# mcu.net
KiCad netlist of a schematic drawn in Altium Designer
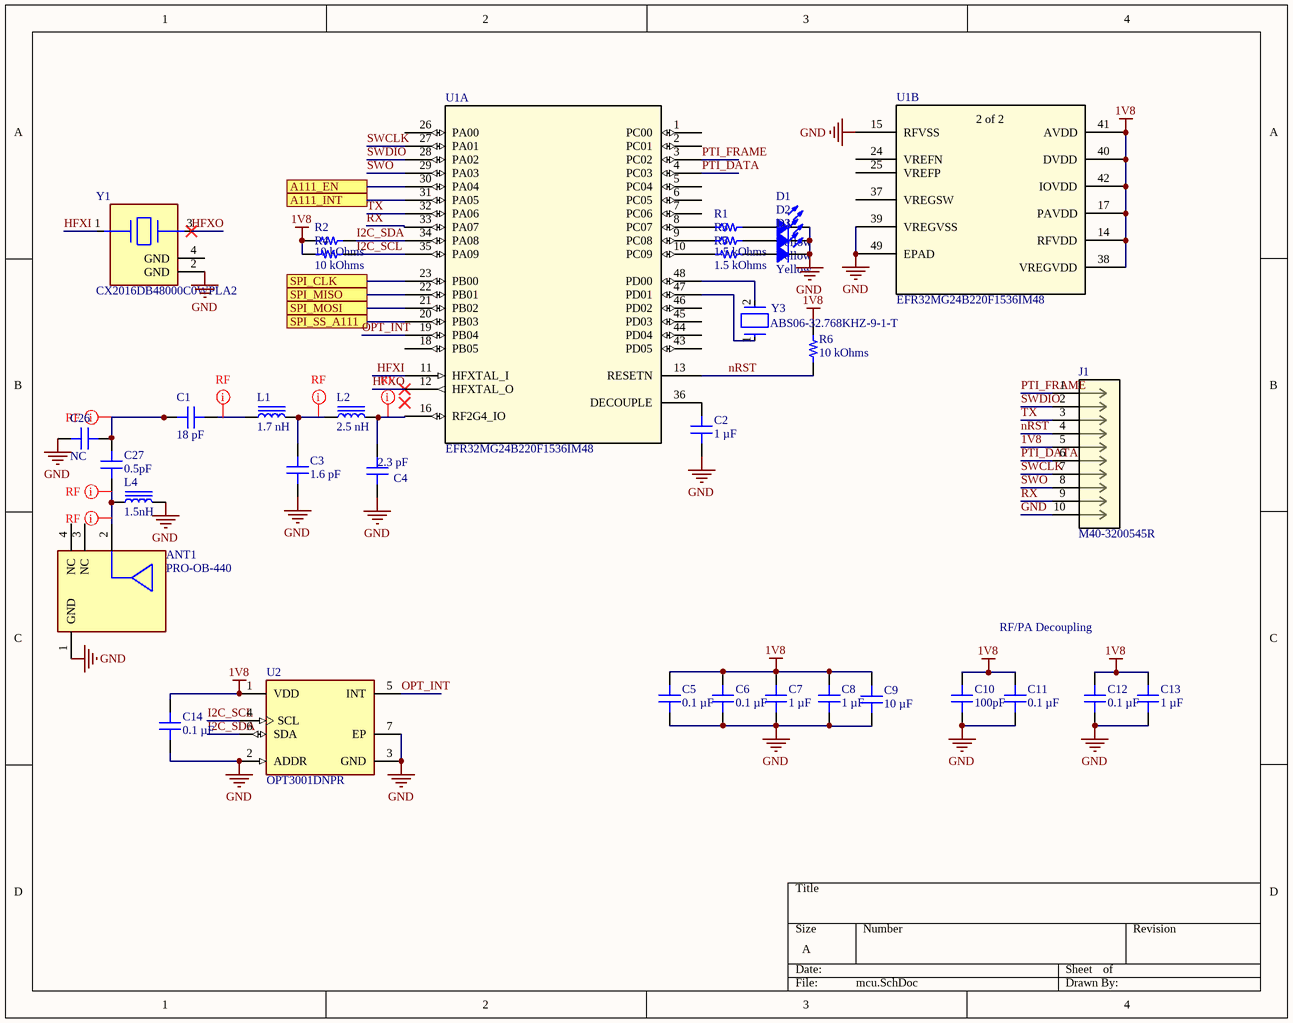
[diagram p0: mcu.SchDoc]

(export (version "E")
  (design (tool "Eeschema 10.0.6"))
  (components
    (comp (ref "ANT1")
      (value "PRO-OB-440")
      (footprint "FP-PRO-OB-440-MFG")
      (description "RF ANT 2.4GHZ STAMPED MET SLD")
      (fields
        (field (name "OCTOPART") "https://octopart.com/pro-ob-440-proant+ab-62921801")
        (field (name "MANUFACTURER") "ProAnt")
      )
      (libsource (lib "Altium Content Vault") (part "a5499d18dbada9eaf90098da4fe60e6"))
    )
    (comp (ref "C1")
      (value "18 pF")
      (footprint "CAP 0402_1005 RF")
      (description "CAP CER 18PF 200V NP0 0402")
      (fields
        (field (name "PART NUMBER") "600L180FW200T")
        (field (name "MANUFACTURER") "American Technical Ceramics")
      )
      (libsource (lib "Celestial Altium Library - altium_library") (part "Capacitor"))
    )
    (comp (ref "C2")
      (value "1 µF")
      (footprint "CAP 0402_1005")
      (description "CAP CER 0.1UF 4V X5R 0402")
      (fields (field (name "PART NUMBER") "C0402C104K7PAC7867") (field (name "MANUFACTURER") "KEMET"))
      (libsource (lib "Celestial Altium Library - altium_library") (part "Capacitor"))
    )
    (comp (ref "C3")
      (value "1.6 pF")
      (footprint "CAP 0402_1005 RF")
      (description "CAP CER 1.6PF 50V C0G/NP0 0402")
      (fields
        (field (name "PART NUMBER") "GJM1555C1H1R6CB01D")
        (field (name "MANUFACTURER") "Murata Electronics")
      )
      (libsource (lib "Celestial Altium Library - altium_library") (part "Capacitor"))
    )
    (comp (ref "C4")
      (value "2.3 pF")
      (footprint "CAP 0402_1005 RF")
      (description "CAP CER 2.3PF 50V C0G/NP0 0402")
      (fields
        (field (name "PART NUMBER") "GJM1555C1H2R3BB01D")
        (field (name "MANUFACTURER") "Murata Electronics")
      )
      (libsource (lib "Celestial Altium Library - altium_library") (part "Capacitor"))
    )
    (comp (ref "C5")
      (value "0.1 µF")
      (footprint "CAP 0402_1005")
      (description "CAP CER 0.1UF 4V X5R 0402")
      (fields (field (name "PART NUMBER") "C0402C104K7PAC7867") (field (name "MANUFACTURER") "KEMET"))
      (libsource (lib "Celestial Altium Library - altium_library") (part "Capacitor"))
    )
    (comp (ref "C6")
      (value "0.1 µF")
      (footprint "CAP 0402_1005")
      (description "CAP CER 0402 0.1UF 16V X7R 10%")
      (fields (field (name "PART NUMBER") "C0402C104K4RECAUTO") (field (name "MANUFACTURER") "KEMET"))
      (libsource (lib "Celestial Altium Library - altium_library") (part "Capacitor"))
    )
    (comp (ref "C7")
      (value "1 µF")
      (footprint "CAP 0402_1005")
      (description "CAP CER 1UF 10V X5R 0402")
      (fields (field (name "PART NUMBER") "LMK105BJ105MVHF") (field (name "MANUFACTURER") "Taiyo Yuden"))
      (libsource (lib "Celestial Altium Library - altium_library") (part "Capacitor"))
    )
    (comp (ref "C8")
      (value "1 µF")
      (footprint "CAP 0402_1005")
      (description "CAP CER 1UF 10V X5R 0402")
      (fields (field (name "PART NUMBER") "LMK105BJ105MVHF") (field (name "MANUFACTURER") "Taiyo Yuden"))
      (libsource (lib "Celestial Altium Library - altium_library") (part "Capacitor"))
    )
    (comp (ref "C9")
      (value "10 µF")
      (footprint "CAP 0603_1608")
      (description "CAP CER 10UF 6.3V X5R 0603")
      (fields
        (field (name "PART NUMBER") "GRM188R60J106ME47D")
        (field (name "MANUFACTURER") "Murata Electronics")
      )
      (libsource (lib "Celestial Altium Library - altium_library") (part "Capacitor"))
    )
    (comp (ref "C10")
      (value "100pF")
      (footprint "CAP 0402_1005")
      (description "CAP CER 100PF 6.3V X7R 0402")
      (fields (field (name "PART NUMBER") "04026C101KAT2A") (field (name "MANUFACTURER") "AVX Corporation"))
      (libsource (lib "Celestial Altium Library - altium_library") (part "Capacitor"))
    )
    (comp (ref "C11")
      (value "0.1 µF")
      (footprint "CAP 0402_1005")
      (description "CAP CER 0.1UF 4V X5R 0402")
      (fields (field (name "PART NUMBER") "C0402C104K7PAC7867") (field (name "MANUFACTURER") "KEMET"))
      (libsource (lib "Celestial Altium Library - altium_library") (part "Capacitor"))
    )
    (comp (ref "C12")
      (value "0.1 µF")
      (footprint "CAP 0402_1005")
      (description "CAP CER 0.1UF 4V X5R 0402")
      (fields (field (name "PART NUMBER") "C0402C104K7PAC7867") (field (name "MANUFACTURER") "KEMET"))
      (libsource (lib "Celestial Altium Library - altium_library") (part "Capacitor"))
    )
    (comp (ref "C13")
      (value "1 µF")
      (footprint "CAP 0402_1005")
      (description "CAP CER 1UF 4V X5R 0402")
      (fields
        (field (name "PART NUMBER") "CGB2T1X5R0G105M022BC")
        (field (name "MANUFACTURER") "TDK Corporation")
      )
      (libsource (lib "Celestial Altium Library - altium_library") (part "Capacitor"))
    )
    (comp (ref "C14")
      (value "0.1 µF")
      (footprint "CAP 0402_1005")
      (description "CAP CER 0.1UF 4V X5R 0402")
      (fields (field (name "PART NUMBER") "C0402C104K7PAC7867") (field (name "MANUFACTURER") "KEMET"))
      (libsource (lib "Celestial Altium Library - altium_library") (part "Capacitor"))
    )
    (comp (ref "C26")
      (value "NC")
      (footprint "CAP 0402_1005 RF")
      (description "CAP CER 18PF 200V NP0 0402")
      (fields
        (field (name "PART NUMBER") "600L180FW200T")
        (field (name "MANUFACTURER") "American Technical Ceramics")
      )
      (libsource (lib "Celestial Altium Library - altium_library") (part "Capacitor"))
    )
    (comp (ref "C27")
      (value "0.5pF")
      (footprint "CAP 0402_1005 RF")
      (description "CAP CER 18PF 200V NP0 0402")
      (fields
        (field (name "PART NUMBER") "600L180FW200T")
        (field (name "MANUFACTURER") "American Technical Ceramics")
      )
      (libsource (lib "Celestial Altium Library - altium_library") (part "Capacitor"))
    )
    (comp (ref "D1")
      (value "Yellow")
      (footprint "LED 0402_1005 YELLOW")
      (description "0402 YELLOW")
      (fields
        (field (name "PART NUMBER") "BL-HKC37A-AV-TRB")
        (field (name "MANUFACTURER") "American Bright Optoelectronics Corporation")
      )
      (libsource (lib "Celestial Altium Library - altium_library") (part "LED"))
    )
    (comp (ref "D2")
      (value "Yellow")
      (footprint "LED 0402_1005 YELLOW")
      (description "0402 YELLOW")
      (fields
        (field (name "PART NUMBER") "BL-HKC37A-AV-TRB")
        (field (name "MANUFACTURER") "American Bright Optoelectronics Corporation")
      )
      (libsource (lib "Celestial Altium Library - altium_library") (part "LED"))
    )
    (comp (ref "D3")
      (value "Yellow")
      (footprint "LED 0402_1005 YELLOW")
      (description "0402 YELLOW")
      (fields
        (field (name "PART NUMBER") "BL-HKC37A-AV-TRB")
        (field (name "MANUFACTURER") "American Bright Optoelectronics Corporation")
      )
      (libsource (lib "Celestial Altium Library - altium_library") (part "LED"))
    )
    (comp (ref "J1")
      (value "M40-3200545R")
      (footprint "CONN10_M40-3200545R_HRW")
      (description "No Description Available")
      (fields (field (name "COPYRIGHT") "Copyright (C) 2022 Ultra Librarian. All rights reserved."))
      (libsource (lib "M40-3200545R") (part "M40-3200545R"))
    )
    (comp (ref "L1")
      (value "1.7 nH")
      (footprint "IND 0402_1005 RF WW")
      (description "FIXED IND 1.7NH 1.15A 65MOHM SMD")
      (fields
        (field (name "PART NUMBER") "LQW15AN1N7D8ZD")
        (field (name "MANUFACTURER") "Murata Electronics")
      )
      (libsource (lib "Celestial Altium Library - altium_library") (part "Inductor"))
    )
    (comp (ref "L2")
      (value "2.5 nH")
      (footprint "IND 0402_1005 RF WW")
      (description "FIXED IND 2.5NH 850MA 50MOHM SMD")
      (fields
        (field (name "PART NUMBER") "LQW15AN2N5B00D")
        (field (name "MANUFACTURER") "Murata Electronics")
      )
      (libsource (lib "Celestial Altium Library - altium_library") (part "Inductor"))
    )
    (comp (ref "L4")
      (value "1.5nH")
      (footprint "IND 0402_1005 RF WW")
      (description "FIXED IND 1.7NH 1.15A 65MOHM SMD")
      (fields
        (field (name "PART NUMBER") "LQW15AN1N7D8ZD")
        (field (name "MANUFACTURER") "Murata Electronics")
      )
      (libsource (lib "Celestial Altium Library - altium_library") (part "Inductor"))
    )
    (comp (ref "R1")
      (value "~")
      (footprint "RES 0402_1005")
      (description "RES 1.5K OHM 0.05% 1/10W 0402")
      (fields
        (field (name "PART NUMBER") "ERA-2VRW1501X")
        (field (name "MANUFACTURER") "Panasonic Electronic Components")
      )
      (libsource (lib "Celestial Altium Library - altium_library") (part "Resistor"))
    )
    (comp (ref "R2")
      (value "10 kOhms")
      (footprint "RES 0402_1005")
      (description "RES 10K OHM 0.1% 1/10W 0402")
      (fields
        (field (name "PART NUMBER") "RP73PF1E10KBTD")
        (field (name "MANUFACTURER") "TE Connectivity Passive Product")
      )
      (libsource (lib "Celestial Altium Library - altium_library") (part "Resistor"))
    )
    (comp (ref "R3")
      (value "1.5 kOhms")
      (footprint "RES 0402_1005")
      (description "RES 1.5K OHM 0.05% 1/10W 0402")
      (fields
        (field (name "PART NUMBER") "ERA-2VRW1501X")
        (field (name "MANUFACTURER") "Panasonic Electronic Components")
      )
      (libsource (lib "Celestial Altium Library - altium_library") (part "Resistor"))
    )
    (comp (ref "R4")
      (value "10 kOhms")
      (footprint "RES 0402_1005")
      (description "RES 10K OHM 0.1% 1/10W 0402")
      (fields
        (field (name "PART NUMBER") "RP73PF1E10KBTD")
        (field (name "MANUFACTURER") "TE Connectivity Passive Product")
      )
      (libsource (lib "Celestial Altium Library - altium_library") (part "Resistor"))
    )
    (comp (ref "R5")
      (value "1.5 kOhms")
      (footprint "RES 0402_1005")
      (description "RES 1.5K OHM 0.05% 1/10W 0402")
      (fields
        (field (name "PART NUMBER") "ERA-2VRW1501X")
        (field (name "MANUFACTURER") "Panasonic Electronic Components")
      )
      (libsource (lib "Celestial Altium Library - altium_library") (part "Resistor"))
    )
    (comp (ref "R6")
      (value "10 kOhms")
      (footprint "RES 0402_1005")
      (description "RES 10K OHM 0.1% 1/10W 0402")
      (fields
        (field (name "PART NUMBER") "RP73PF1E10KBTD")
        (field (name "MANUFACTURER") "TE Connectivity Passive Product")
      )
      (libsource (lib "Celestial Altium Library - altium_library") (part "Resistor"))
    )
    (comp (ref "U1")
      (value "EFR32MG24B220F1536IM48")
      (footprint "QFN48_0p4_6sq_SIL")
      (description "No Description Available")
      (fields (field (name "COPYRIGHT") "Copyright (C) 2022 Ultra Librarian. All rights reserved."))
      (libsource (lib "EFR32MG24B220F1536IM48") (part "EFR32MG24B220F1536IM48"))
    )
    (comp (ref "U2")
      (value "OPT3001DNPR")
      (footprint "FP-DNP0006A-MFG")
      (description "SENSOR OPT 550NM AMBIENT 6USON")
      (fields
        (field (name "OCTOPART") "https://octopart.com/opt3001dnpr-texas+instruments-47324050")
        (field (name "MANUFACTURER") "Texas Instruments")
      )
      (libsource (lib "Altium Content Vault") (part "6d36863dc75c3adee7e1b5a0d97a822"))
    )
    (comp (ref "Y1")
      (value "CX2016DB48000C0WPLA2")
      (footprint "FP-CX2016DB48000C0WPLA2-MFG")
      (description "CRYSTAL 48.0000MHZ 7PF SMD")
      (fields
        (field (name "TOLERANCE") "20ppm")
        (field (name "OCTOPART") "https://octopart.com/cx2016db48000c0wpla2-avx+%2F+kyocera-52876167")
      )
      (libsource (lib "Altium Content Vault") (part "5d94e547cd785c846f3f8944f2e9776"))
    )
    (comp (ref "Y3")
      (value "ABS06-32.768KHZ-9-1-T")
      (footprint "FP-ABS06-MFG")
      (description "Crystal 32.768kHz ±10ppm (Tol) 9pF FUND 90kΩ 2-Pin Mini-CSMD T/R")
      (fields (field (name "TOLERANCE") "10ppm"))
      (libsource (lib "Altium Content Vault") (part "c23a69dc6c9e2f18f2079038eb95dd1"))
    )
  )
  (nets
    (net (code "1") (name "/A111_EN") (class "Default")
      (node (ref "U1") (pin "30") (pinfunction "PA04_30") (pintype "bidirectional"))
    )
    (net (code "2") (name "/A111_INT") (class "Default")
      (node (ref "U1") (pin "31") (pinfunction "PA05_31") (pintype "bidirectional"))
    )
    (net (code "3") (name "/HFXI") (class "Default")
      (node (ref "U1") (pin "11") (pinfunction "HFXTAL_I_11") (pintype "input"))
      (node (ref "Y1") (pin "1") (pinfunction "1_HOT_1") (pintype "passive"))
    )
    (net (code "4") (name "/HFXO") (class "Default")
      (node (ref "U1") (pin "12") (pinfunction "HFXTAL_O_12") (pintype "output"))
      (node (ref "Y1") (pin "3") (pinfunction "2_HOT_3") (pintype "passive"))
    )
    (net (code "5") (name "/I2C_SCL") (class "Default")
      (node (ref "R4") (pin "1") (pinfunction "1_1") (pintype "passive"))
      (node (ref "U1") (pin "35") (pinfunction "PA09_35") (pintype "bidirectional"))
      (node (ref "U2") (pin "4") (pinfunction "SCL_4") (pintype "input"))
    )
    (net (code "6") (name "/I2C_SDA") (class "Default")
      (node (ref "R2") (pin "1") (pinfunction "1_1") (pintype "passive"))
      (node (ref "U1") (pin "34") (pinfunction "PA08_34") (pintype "bidirectional"))
      (node (ref "U2") (pin "6") (pinfunction "SDA_6") (pintype "bidirectional"))
    )
    (net (code "7") (name "/OPT_INT") (class "Default")
      (node (ref "U1") (pin "19") (pinfunction "PB04_19") (pintype "bidirectional"))
      (node (ref "U2") (pin "5") (pinfunction "INT_5") (pintype "open_collector"))
    )
    (net (code "8") (name "/PTI_DATA") (class "Default")
      (node (ref "J1") (pin "6") (pinfunction "6_6") (pintype "passive"))
      (node (ref "U1") (pin "4") (pinfunction "PC03_4") (pintype "bidirectional"))
    )
    (net (code "9") (name "/PTI_FRAME") (class "Default")
      (node (ref "J1") (pin "1") (pinfunction "1_1") (pintype "passive"))
      (node (ref "U1") (pin "3") (pinfunction "PC02_3") (pintype "bidirectional"))
    )
    (net (code "10") (name "/RX") (class "Default")
      (node (ref "J1") (pin "9") (pinfunction "9_9") (pintype "passive"))
      (node (ref "U1") (pin "33") (pinfunction "PA07_33") (pintype "bidirectional"))
    )
    (net (code "11") (name "/SPI_CLK") (class "Default")
      (node (ref "U1") (pin "23") (pinfunction "PB00_23") (pintype "bidirectional"))
    )
    (net (code "12") (name "/SPI_MISO") (class "Default")
      (node (ref "U1") (pin "22") (pinfunction "PB01_22") (pintype "bidirectional"))
    )
    (net (code "13") (name "/SPI_MOSI") (class "Default")
      (node (ref "U1") (pin "21") (pinfunction "PB02_21") (pintype "bidirectional"))
    )
    (net (code "14") (name "/SPI_SS_A111") (class "Default")
      (node (ref "U1") (pin "20") (pinfunction "PB03_20") (pintype "bidirectional"))
    )
    (net (code "15") (name "/SWCLK") (class "Default")
      (node (ref "J1") (pin "7") (pinfunction "7_7") (pintype "passive"))
      (node (ref "U1") (pin "27") (pinfunction "PA01_27") (pintype "bidirectional"))
    )
    (net (code "16") (name "/SWDIO") (class "Default")
      (node (ref "J1") (pin "2") (pinfunction "2_2") (pintype "passive"))
      (node (ref "U1") (pin "28") (pinfunction "PA02_28") (pintype "bidirectional"))
    )
    (net (code "17") (name "/SWO") (class "Default")
      (node (ref "J1") (pin "8") (pinfunction "8_8") (pintype "passive"))
      (node (ref "U1") (pin "29") (pinfunction "PA03_29") (pintype "bidirectional"))
    )
    (net (code "18") (name "/TX") (class "Default")
      (node (ref "J1") (pin "3") (pinfunction "3_3") (pintype "passive"))
      (node (ref "U1") (pin "32") (pinfunction "PA06_32") (pintype "bidirectional"))
    )
    (net (code "19") (name "/nRST") (class "Default")
      (node (ref "J1") (pin "4") (pinfunction "4_4") (pintype "passive"))
      (node (ref "R6") (pin "2") (pinfunction "2_2") (pintype "passive"))
      (node (ref "U1") (pin "13") (pinfunction "RESETN_13") (pintype "passive"))
    )
    (net (code "20") (name "1V8") (class "Default")
      (node (ref "C10") (pin "2") (pinfunction "2_2") (pintype "passive"))
      (node (ref "C11") (pin "2") (pinfunction "2_2") (pintype "passive"))
      (node (ref "C12") (pin "2") (pinfunction "2_2") (pintype "passive"))
      (node (ref "C13") (pin "2") (pinfunction "2_2") (pintype "passive"))
      (node (ref "C14") (pin "2") (pinfunction "2_2") (pintype "passive"))
      (node (ref "C5") (pin "2") (pinfunction "2_2") (pintype "passive"))
      (node (ref "C6") (pin "2") (pinfunction "2_2") (pintype "passive"))
      (node (ref "C7") (pin "2") (pinfunction "2_2") (pintype "passive"))
      (node (ref "C8") (pin "2") (pinfunction "2_2") (pintype "passive"))
      (node (ref "C9") (pin "2") (pinfunction "2_2") (pintype "passive"))
      (node (ref "J1") (pin "5") (pinfunction "5_5") (pintype "passive"))
      (node (ref "R2") (pin "2") (pinfunction "2_2") (pintype "passive"))
      (node (ref "R4") (pin "2") (pinfunction "2_2") (pintype "passive"))
      (node (ref "R6") (pin "1") (pinfunction "1_1") (pintype "passive"))
      (node (ref "U1") (pin "14") (pinfunction "RFVDD_14") (pintype "power_in"))
      (node (ref "U1") (pin "17") (pinfunction "PAVDD_17") (pintype "power_in"))
      (node (ref "U1") (pin "38") (pinfunction "VREGVDD_38") (pintype "power_in"))
      (node (ref "U1") (pin "40") (pinfunction "DVDD_40") (pintype "power_in"))
      (node (ref "U1") (pin "41") (pinfunction "AVDD_41") (pintype "power_in"))
      (node (ref "U1") (pin "42") (pinfunction "IOVDD_42") (pintype "power_in"))
      (node (ref "U2") (pin "1") (pinfunction "VDD_1") (pintype "power_in"))
    )
    (net (code "21") (name "GND") (class "Default")
      (node (ref "ANT1") (pin "1") (pinfunction "GND_1") (pintype "power_in"))
      (node (ref "C10") (pin "1") (pinfunction "1_1") (pintype "passive"))
      (node (ref "C11") (pin "1") (pinfunction "1_1") (pintype "passive"))
      (node (ref "C12") (pin "1") (pinfunction "1_1") (pintype "passive"))
      (node (ref "C13") (pin "1") (pinfunction "1_1") (pintype "passive"))
      (node (ref "C14") (pin "1") (pinfunction "1_1") (pintype "passive"))
      (node (ref "C2") (pin "1") (pinfunction "1_1") (pintype "passive"))
      (node (ref "C26") (pin "1") (pinfunction "1_1") (pintype "passive"))
      (node (ref "C3") (pin "1") (pinfunction "1_1") (pintype "passive"))
      (node (ref "C4") (pin "1") (pinfunction "1_1") (pintype "passive"))
      (node (ref "C5") (pin "1") (pinfunction "1_1") (pintype "passive"))
      (node (ref "C6") (pin "1") (pinfunction "1_1") (pintype "passive"))
      (node (ref "C7") (pin "1") (pinfunction "1_1") (pintype "passive"))
      (node (ref "C8") (pin "1") (pinfunction "1_1") (pintype "passive"))
      (node (ref "C9") (pin "1") (pinfunction "1_1") (pintype "passive"))
      (node (ref "D1") (pin "2") (pinfunction "2_2") (pintype "passive"))
      (node (ref "D2") (pin "2") (pinfunction "2_2") (pintype "passive"))
      (node (ref "D3") (pin "2") (pinfunction "2_2") (pintype "passive"))
      (node (ref "J1") (pin "10") (pinfunction "10_10") (pintype "passive"))
      (node (ref "L4") (pin "2") (pinfunction "2_2") (pintype "passive"))
      (node (ref "U1") (pin "15") (pinfunction "RFVSS_15") (pintype "power_in"))
      (node (ref "U1") (pin "39") (pinfunction "VREGVSS_39") (pintype "power_in"))
      (node (ref "U1") (pin "49") (pinfunction "EPAD_49") (pintype "passive"))
      (node (ref "U2") (pin "2") (pinfunction "ADDR_2") (pintype "input"))
      (node (ref "U2") (pin "3") (pinfunction "GND_3") (pintype "power_in"))
      (node (ref "U2") (pin "7") (pinfunction "EP_7") (pintype "power_in"))
      (node (ref "Y1") (pin "2") (pinfunction "GND_2") (pintype "power_in"))
    )
    (net (code "22") (name "Net-(ANT1-RF_FEED)") (class "Default")
      (node (ref "ANT1") (pin "2") (pinfunction "RF_FEED_2") (pintype "passive"))
      (node (ref "C27") (pin "1") (pinfunction "1_1") (pintype "passive"))
      (node (ref "L4") (pin "1") (pinfunction "1_1") (pintype "passive"))
    )
    (net (code "23") (name "Net-(C1-Pad1)") (class "Default")
      (node (ref "C1") (pin "1") (pinfunction "1_1") (pintype "passive"))
      (node (ref "C26") (pin "2") (pinfunction "2_2") (pintype "passive"))
      (node (ref "C27") (pin "2") (pinfunction "2_2") (pintype "passive"))
    )
    (net (code "24") (name "Net-(C1-Pad2)") (class "Default")
      (node (ref "C1") (pin "2") (pinfunction "2_2") (pintype "passive"))
      (node (ref "L1") (pin "1") (pinfunction "1_1") (pintype "passive"))
    )
    (net (code "25") (name "Net-(C3-Pad2)") (class "Default")
      (node (ref "C3") (pin "2") (pinfunction "2_2") (pintype "passive"))
      (node (ref "L1") (pin "2") (pinfunction "2_2") (pintype "passive"))
      (node (ref "L2") (pin "1") (pinfunction "1_1") (pintype "passive"))
    )
    (net (code "26") (name "Net-(D1-Pad1)") (class "Default")
      (node (ref "D1") (pin "1") (pinfunction "1_1") (pintype "passive"))
      (node (ref "R1") (pin "1") (pinfunction "1_1") (pintype "passive"))
    )
    (net (code "27") (name "Net-(D2-Pad1)") (class "Default")
      (node (ref "D2") (pin "1") (pinfunction "1_1") (pintype "passive"))
      (node (ref "R3") (pin "1") (pinfunction "1_1") (pintype "passive"))
    )
    (net (code "28") (name "Net-(D3-Pad1)") (class "Default")
      (node (ref "D3") (pin "1") (pinfunction "1_1") (pintype "passive"))
      (node (ref "R5") (pin "1") (pinfunction "1_1") (pintype "passive"))
    )
    (net (code "29") (name "Net-(U1A-DECOUPLE)") (class "Default")
      (node (ref "C2") (pin "2") (pinfunction "2_2") (pintype "passive"))
      (node (ref "U1") (pin "36") (pinfunction "DECOUPLE_36") (pintype "passive"))
    )
    (net (code "30") (name "Net-(U1A-PC07)") (class "Default")
      (node (ref "R1") (pin "2") (pinfunction "2_2") (pintype "passive"))
      (node (ref "U1") (pin "8") (pinfunction "PC07_8") (pintype "bidirectional"))
    )
    (net (code "31") (name "Net-(U1A-PC08)") (class "Default")
      (node (ref "R3") (pin "2") (pinfunction "2_2") (pintype "passive"))
      (node (ref "U1") (pin "9") (pinfunction "PC08_9") (pintype "bidirectional"))
    )
    (net (code "32") (name "Net-(U1A-PC09)") (class "Default")
      (node (ref "R5") (pin "2") (pinfunction "2_2") (pintype "passive"))
      (node (ref "U1") (pin "10") (pinfunction "PC09_10") (pintype "bidirectional"))
    )
    (net (code "33") (name "Net-(U1A-PD00)") (class "Default")
      (node (ref "U1") (pin "48") (pinfunction "PD00_48") (pintype "bidirectional"))
      (node (ref "Y3") (pin "2") (pinfunction "2_2") (pintype "passive"))
    )
    (net (code "34") (name "Net-(U1A-PD01)") (class "Default")
      (node (ref "U1") (pin "47") (pinfunction "PD01_47") (pintype "bidirectional"))
      (node (ref "Y3") (pin "1") (pinfunction "1_1") (pintype "passive"))
    )
    (net (code "35") (name "Net-(U1A-RF2G4_IO)") (class "Default")
      (node (ref "C4") (pin "2") (pinfunction "2_2") (pintype "passive"))
      (node (ref "L2") (pin "2") (pinfunction "2_2") (pintype "passive"))
      (node (ref "U1") (pin "16") (pinfunction "RF2G4_IO_16") (pintype "bidirectional"))
    )
    (net (code "36") (name "unconnected-(ANT1-NC-Pad3)") (class "Default")
      (node (ref "ANT1") (pin "3") (pinfunction "NC_3") (pintype "passive"))
    )
    (net (code "37") (name "unconnected-(ANT1-NC-Pad4)") (class "Default")
      (node (ref "ANT1") (pin "4") (pinfunction "NC_4") (pintype "passive"))
    )
    (net (code "38") (name "unconnected-(U1A-PA00-Pad26)") (class "Default")
      (node (ref "U1") (pin "26") (pinfunction "PA00_26") (pintype "bidirectional"))
    )
    (net (code "39") (name "unconnected-(U1A-PB05-Pad18)") (class "Default")
      (node (ref "U1") (pin "18") (pinfunction "PB05_18") (pintype "bidirectional"))
    )
    (net (code "40") (name "unconnected-(U1A-PC00-Pad1)") (class "Default")
      (node (ref "U1") (pin "1") (pinfunction "PC00_1") (pintype "bidirectional"))
    )
    (net (code "41") (name "unconnected-(U1A-PC01-Pad2)") (class "Default")
      (node (ref "U1") (pin "2") (pinfunction "PC01_2") (pintype "bidirectional"))
    )
    (net (code "42") (name "unconnected-(U1A-PC04-Pad5)") (class "Default")
      (node (ref "U1") (pin "5") (pinfunction "PC04_5") (pintype "bidirectional"))
    )
    (net (code "43") (name "unconnected-(U1A-PC05-Pad6)") (class "Default")
      (node (ref "U1") (pin "6") (pinfunction "PC05_6") (pintype "bidirectional"))
    )
    (net (code "44") (name "unconnected-(U1A-PC06-Pad7)") (class "Default")
      (node (ref "U1") (pin "7") (pinfunction "PC06_7") (pintype "bidirectional"))
    )
    (net (code "45") (name "unconnected-(U1A-PD02-Pad46)") (class "Default")
      (node (ref "U1") (pin "46") (pinfunction "PD02_46") (pintype "bidirectional"))
    )
    (net (code "46") (name "unconnected-(U1A-PD03-Pad45)") (class "Default")
      (node (ref "U1") (pin "45") (pinfunction "PD03_45") (pintype "bidirectional"))
    )
    (net (code "47") (name "unconnected-(U1A-PD04-Pad44)") (class "Default")
      (node (ref "U1") (pin "44") (pinfunction "PD04_44") (pintype "bidirectional"))
    )
    (net (code "48") (name "unconnected-(U1A-PD05-Pad43)") (class "Default")
      (node (ref "U1") (pin "43") (pinfunction "PD05_43") (pintype "bidirectional"))
    )
    (net (code "49") (name "unconnected-(U1B-VREFN-Pad24)") (class "Default")
      (node (ref "U1") (pin "24") (pinfunction "VREFN_24") (pintype "power_in"))
    )
    (net (code "50") (name "unconnected-(U1B-VREFP-Pad25)") (class "Default")
      (node (ref "U1") (pin "25") (pinfunction "VREFP_25") (pintype "power_in"))
    )
    (net (code "51") (name "unconnected-(U1B-VREGSW-Pad37)") (class "Default")
      (node (ref "U1") (pin "37") (pinfunction "VREGSW_37") (pintype "power_in"))
    )
    (net (code "52") (name "unconnected-(Y1-GND-Pad4)") (class "Default")
      (node (ref "Y1") (pin "4") (pinfunction "GND_4") (pintype "power_in"))
    )
  )
)
